# GPS_SCHE.net
KiCad netlist of a schematic drawn in Altium Designer
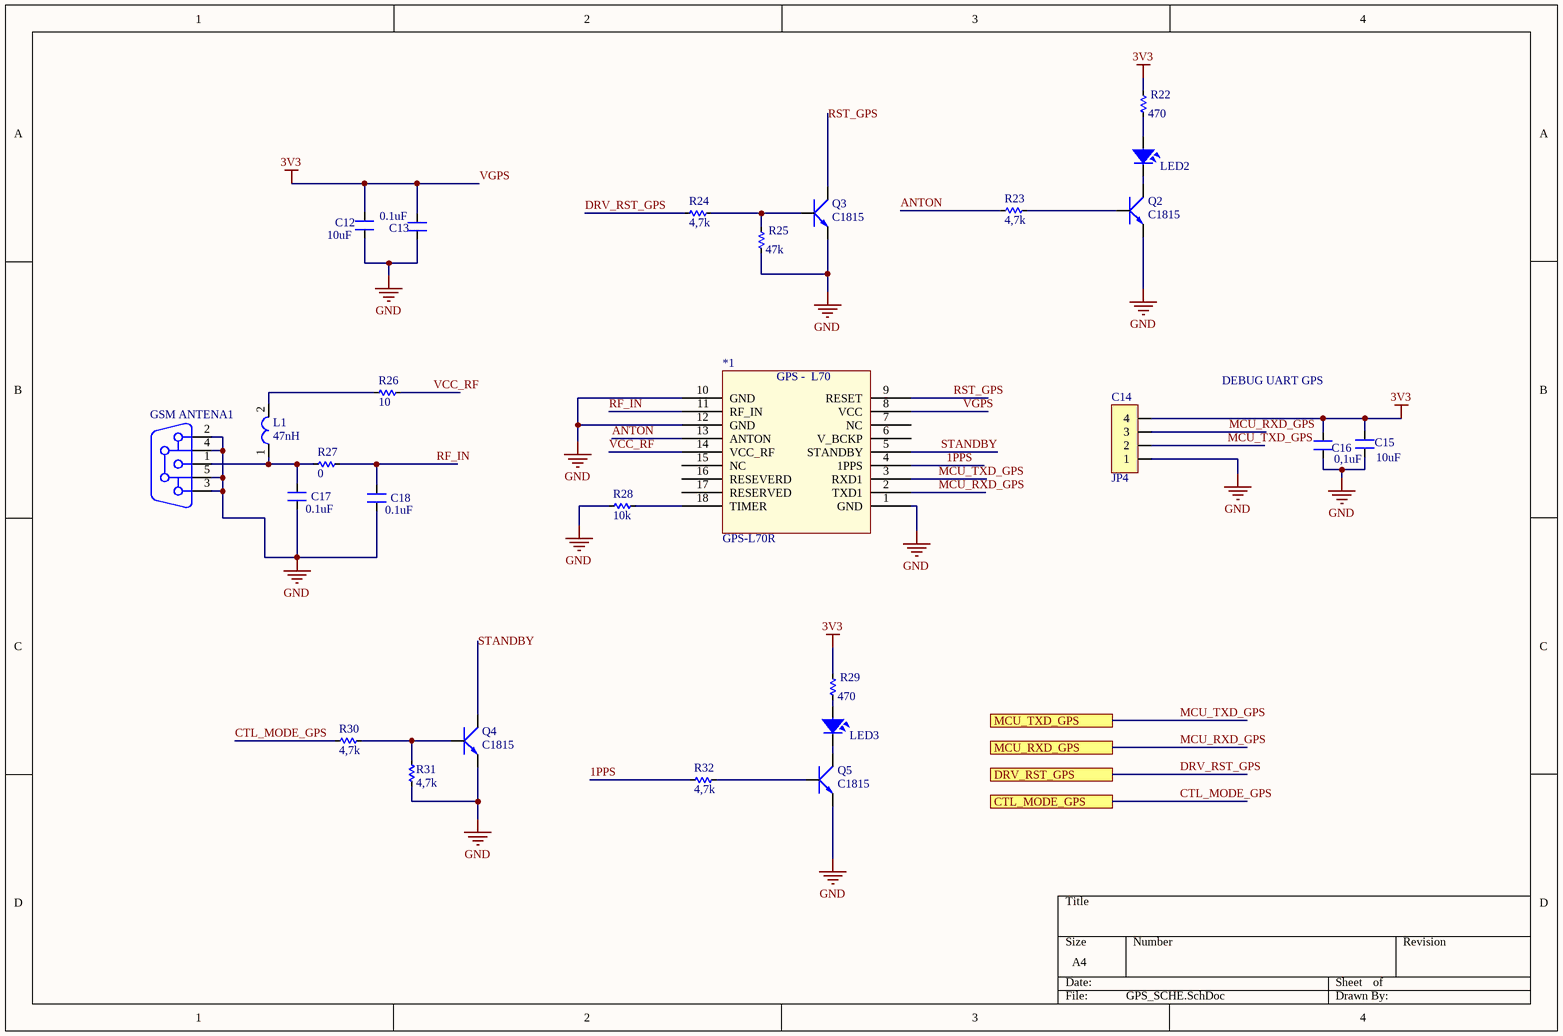
[diagram p0: GPS_SCHE.SchDoc]

(export (version "E")
  (design (tool "Eeschema 10.0.6"))
  (components
    (comp (ref "*1") (value "GPS-L70R") (footprint "GPS_L70R") (libsource (lib "Sim M95") (part "GPS-L70")))
    (comp (ref "C12")
      (value "10uF")
      (footprint "res 0805 - duplicate")
      (fields (field (name "DESIGNED BY") "VanDungEvn"))
      (libsource (lib "syhaunguyen") (part "CN"))
    )
    (comp (ref "C13")
      (value "0.1uF")
      (footprint "res 0805 - duplicate")
      (description "Cap SMD")
      (libsource (lib "PART") (part "CM"))
    )
    (comp (ref "C14")
      (value "JP4")
      (footprint "JP4-C1T")
      (description "WR-PHD 2.54 mm Angled Socket Header")
      (fields
        (field (name "MANUFACTURER") "Würth Elektronik eiSos GmbH")
        (field (name "PARTNO") "613004143121")
        (field (name "CREATED BY") "Karrer Zheng")
      )
      (libsource (lib "LIBRARYabc") (part "JP4"))
    )
    (comp (ref "C15")
      (value "10uF")
      (footprint "res 0805 - duplicate")
      (fields (field (name "DESIGNED BY") "VanDungEvn"))
      (libsource (lib "syhaunguyen") (part "CN"))
    )
    (comp (ref "C16")
      (value "0,1uF")
      (footprint "res 0805 - duplicate")
      (fields (field (name "DESIGNED BY") "VanDungEvn"))
      (libsource (lib "syhaunguyen") (part "CN"))
    )
    (comp (ref "C17")
      (value "0.1uF")
      (footprint "res 0805 - duplicate")
      (description "Cap SMD")
      (libsource (lib "PART") (part "CM"))
    )
    (comp (ref "C18")
      (value "0.1uF")
      (footprint "res 0805 - duplicate")
      (description "Cap SMD")
      (libsource (lib "PART") (part "CM"))
    )
    (comp (ref "GSM ANTENA1")
      (value "~")
      (footprint "anten")
      (description "CONNECTOR ANTEN")
      (fields
        (field (name "PARTNO") "210111003")
        (field (name "MANUFACTURER") "Würth Elektronik eiSos GmbH")
        (field (name "CREATED BY") "Christin Zierenner")
      )
      (libsource (lib "LIBRARYabc") (part "CON Ant"))
    )
    (comp (ref "L1")
      (value "47nH")
      (footprint "res 0805 - duplicate")
      (fields
        (field (name "PARTNO") "78477010")
        (field (name "MANUFACTURER") "Wurth Elektronik")
        (field (name "CREATED BY") "Baojun Chen")
      )
      (libsource (lib "LIBRARYabc") (part "L-SMD-1"))
    )
    (comp (ref "LED2")
      (value "LED")
      (footprint "res 0805 - duplicate")
      (libsource (lib "LIBRARYabc") (part "LED SMD"))
    )
    (comp (ref "LED3")
      (value "LED")
      (footprint "res 0805 - duplicate")
      (libsource (lib "LIBRARYabc") (part "LED SMD"))
    )
    (comp (ref "Q2")
      (value "C1815")
      (footprint "SOT23B")
      (description "NPN 600mW, ECB")
      (libsource (lib "syhaunguyen") (part "C1815"))
    )
    (comp (ref "Q3")
      (value "C1815")
      (footprint "SOT23B")
      (description "NPN 600mW, ECB")
      (libsource (lib "syhaunguyen") (part "C1815"))
    )
    (comp (ref "Q4")
      (value "C1815")
      (footprint "SOT23B")
      (description "NPN 600mW, ECB")
      (libsource (lib "syhaunguyen") (part "C1815"))
    )
    (comp (ref "Q5")
      (value "C1815")
      (footprint "SOT23B")
      (description "NPN 600mW, ECB")
      (libsource (lib "syhaunguyen") (part "C1815"))
    )
    (comp (ref "R22")
      (value "470")
      (footprint "res 0805 - duplicate")
      (description "Resistor")
      (fields
        (field (name "MANUFACTURER") "Generic Components")
        (field (name "PUBLISHER") "Altium Hobart Technology Centre")
      )
      (libsource (lib "LIBRARYabc") (part "Res-SMD"))
    )
    (comp (ref "R23")
      (value "4,7k")
      (footprint "res 0805 - duplicate")
      (description "Resistor")
      (fields
        (field (name "MANUFACTURER") "Generic Components")
        (field (name "PUBLISHER") "Altium Hobart Technology Centre")
      )
      (libsource (lib "LIBRARYabc") (part "Res-SMD"))
    )
    (comp (ref "R24")
      (value "4,7k")
      (footprint "res 0805 - duplicate")
      (description "Resistor")
      (fields
        (field (name "MANUFACTURER") "Generic Components")
        (field (name "PUBLISHER") "Altium Hobart Technology Centre")
      )
      (libsource (lib "LIBRARYabc") (part "Res-SMD"))
    )
    (comp (ref "R25")
      (value "47k")
      (footprint "res 0805 - duplicate")
      (description "Resistor")
      (fields
        (field (name "MANUFACTURER") "Generic Components")
        (field (name "PUBLISHER") "Altium Hobart Technology Centre")
      )
      (libsource (lib "LIBRARYabc") (part "Res-SMD"))
    )
    (comp (ref "R26")
      (value "10")
      (footprint "res 0805 - duplicate")
      (description "Resistor")
      (fields
        (field (name "MANUFACTURER") "Generic Components")
        (field (name "PUBLISHER") "Altium Hobart Technology Centre")
      )
      (libsource (lib "LIBRARYabc") (part "Res-SMD"))
    )
    (comp (ref "R27")
      (value "0")
      (footprint "res 0805 - duplicate")
      (description "Resistor")
      (fields
        (field (name "MANUFACTURER") "Generic Components")
        (field (name "PUBLISHER") "Altium Hobart Technology Centre")
      )
      (libsource (lib "LIBRARYabc") (part "Res-SMD"))
    )
    (comp (ref "R28")
      (value "10k")
      (footprint "res 0805 - duplicate")
      (description "Resistor")
      (fields
        (field (name "MANUFACTURER") "Generic Components")
        (field (name "PUBLISHER") "Altium Hobart Technology Centre")
      )
      (libsource (lib "LIBRARYabc") (part "Res-SMD"))
    )
    (comp (ref "R29")
      (value "470")
      (footprint "res 0805 - duplicate")
      (description "Resistor")
      (fields
        (field (name "MANUFACTURER") "Generic Components")
        (field (name "PUBLISHER") "Altium Hobart Technology Centre")
      )
      (libsource (lib "LIBRARYabc") (part "Res-SMD"))
    )
    (comp (ref "R30")
      (value "4,7k")
      (footprint "res 0805 - duplicate")
      (description "Resistor")
      (fields
        (field (name "MANUFACTURER") "Generic Components")
        (field (name "PUBLISHER") "Altium Hobart Technology Centre")
      )
      (libsource (lib "LIBRARYabc") (part "Res-SMD"))
    )
    (comp (ref "R31")
      (value "4,7k")
      (footprint "res 0805 - duplicate")
      (description "Resistor")
      (fields
        (field (name "MANUFACTURER") "Generic Components")
        (field (name "PUBLISHER") "Altium Hobart Technology Centre")
      )
      (libsource (lib "LIBRARYabc") (part "Res-SMD"))
    )
    (comp (ref "R32")
      (value "4,7k")
      (footprint "res 0805 - duplicate")
      (description "Resistor")
      (fields
        (field (name "MANUFACTURER") "Generic Components")
        (field (name "PUBLISHER") "Altium Hobart Technology Centre")
      )
      (libsource (lib "LIBRARYabc") (part "Res-SMD"))
    )
  )
  (nets
    (net (code "1") (name "/1PPS") (class "Default")
      (node (ref "*1") (pin "4") (pinfunction "1PPS_4") (pintype "passive"))
      (node (ref "R32") (pin "1") (pinfunction "1_1") (pintype "passive"))
    )
    (net (code "2") (name "/ANTON") (class "Default")
      (node (ref "*1") (pin "13") (pinfunction "ANTON_13") (pintype "passive"))
      (node (ref "R23") (pin "1") (pinfunction "1_1") (pintype "passive"))
    )
    (net (code "3") (name "/CTL_MODE_GPS") (class "Default")
      (node (ref "R30") (pin "1") (pinfunction "1_1") (pintype "passive"))
    )
    (net (code "4") (name "/DRV_RST_GPS") (class "Default")
      (node (ref "R24") (pin "1") (pinfunction "1_1") (pintype "passive"))
    )
    (net (code "5") (name "/MCU_RXD_GPS") (class "Default")
      (node (ref "*1") (pin "2") (pinfunction "TXD1_2") (pintype "passive"))
      (node (ref "C14") (pin "3") (pinfunction "3_3") (pintype "passive"))
    )
    (net (code "6") (name "/MCU_TXD_GPS") (class "Default")
      (node (ref "*1") (pin "3") (pinfunction "RXD1_3") (pintype "passive"))
      (node (ref "C14") (pin "2") (pinfunction "2_2") (pintype "passive"))
    )
    (net (code "7") (name "/RF_IN") (class "Default")
      (node (ref "*1") (pin "11") (pinfunction "RF_IN_11") (pintype "passive"))
      (node (ref "C18") (pin "2") (pinfunction "2_2") (pintype "passive"))
      (node (ref "R27") (pin "2") (pinfunction "2_2") (pintype "passive"))
    )
    (net (code "8") (name "/RST_GPS") (class "Default")
      (node (ref "*1") (pin "9") (pinfunction "RESET_9") (pintype "passive"))
      (node (ref "Q3") (pin "2") (pinfunction "C_2") (pintype "passive"))
    )
    (net (code "9") (name "/STANDBY") (class "Default")
      (node (ref "*1") (pin "5") (pinfunction "STANDBY_5") (pintype "passive"))
      (node (ref "Q4") (pin "2") (pinfunction "C_2") (pintype "passive"))
    )
    (net (code "10") (name "/VCC_RF") (class "Default")
      (node (ref "*1") (pin "14") (pinfunction "VCC_RF_14") (pintype "passive"))
      (node (ref "R26") (pin "2") (pinfunction "2_2") (pintype "passive"))
    )
    (net (code "11") (name "3V3") (class "Default")
      (node (ref "*1") (pin "8") (pinfunction "VCC_8") (pintype "passive"))
      (node (ref "C12") (pin "2") (pinfunction "2_2") (pintype "passive"))
      (node (ref "C13") (pin "2") (pinfunction "2_2") (pintype "passive"))
      (node (ref "C14") (pin "4") (pinfunction "4_4") (pintype "passive"))
      (node (ref "C15") (pin "2") (pinfunction "2_2") (pintype "passive"))
      (node (ref "C16") (pin "2") (pinfunction "2_2") (pintype "passive"))
      (node (ref "R22") (pin "2") (pinfunction "2_2") (pintype "passive"))
      (node (ref "R29") (pin "2") (pinfunction "2_2") (pintype "passive"))
    )
    (net (code "12") (name "GND") (class "Default")
      (node (ref "*1") (pin "1") (pinfunction "GND_1") (pintype "passive"))
      (node (ref "*1") (pin "10") (pinfunction "GND_10") (pintype "passive"))
      (node (ref "*1") (pin "12") (pinfunction "GND_12") (pintype "passive"))
      (node (ref "C12") (pin "1") (pinfunction "1_1") (pintype "passive"))
      (node (ref "C13") (pin "1") (pinfunction "1_1") (pintype "passive"))
      (node (ref "C14") (pin "1") (pinfunction "1_1") (pintype "passive"))
      (node (ref "C15") (pin "1") (pinfunction "1_1") (pintype "passive"))
      (node (ref "C16") (pin "1") (pinfunction "1_1") (pintype "passive"))
      (node (ref "C17") (pin "1") (pinfunction "1_1") (pintype "passive"))
      (node (ref "C18") (pin "1") (pinfunction "1_1") (pintype "passive"))
      (node (ref "GSM ANTENA1") (pin "2") (pinfunction "2_2") (pintype "passive"))
      (node (ref "GSM ANTENA1") (pin "3") (pinfunction "3_3") (pintype "passive"))
      (node (ref "GSM ANTENA1") (pin "4") (pinfunction "4_4") (pintype "passive"))
      (node (ref "GSM ANTENA1") (pin "5") (pinfunction "5_5") (pintype "passive"))
      (node (ref "Q2") (pin "1") (pinfunction "E_1") (pintype "passive"))
      (node (ref "Q3") (pin "1") (pinfunction "E_1") (pintype "passive"))
      (node (ref "Q4") (pin "1") (pinfunction "E_1") (pintype "passive"))
      (node (ref "Q5") (pin "1") (pinfunction "E_1") (pintype "passive"))
      (node (ref "R25") (pin "1") (pinfunction "1_1") (pintype "passive"))
      (node (ref "R28") (pin "1") (pinfunction "1_1") (pintype "passive"))
      (node (ref "R31") (pin "1") (pinfunction "1_1") (pintype "passive"))
    )
    (net (code "13") (name "Net-(*1-TIMER)") (class "Default")
      (node (ref "*1") (pin "18") (pinfunction "TIMER_18") (pintype "passive"))
      (node (ref "R28") (pin "2") (pinfunction "2_2") (pintype "passive"))
    )
    (net (code "14") (name "Net-(C17-Pad2)") (class "Default")
      (node (ref "C17") (pin "2") (pinfunction "2_2") (pintype "passive"))
      (node (ref "GSM ANTENA1") (pin "1") (pinfunction "1_1") (pintype "passive"))
      (node (ref "L1") (pin "1") (pinfunction "1_1") (pintype "passive"))
      (node (ref "R27") (pin "1") (pinfunction "1_1") (pintype "passive"))
    )
    (net (code "15") (name "Net-(L1-Pad2)") (class "Default")
      (node (ref "L1") (pin "2") (pinfunction "2_2") (pintype "passive"))
      (node (ref "R26") (pin "1") (pinfunction "1_1") (pintype "passive"))
    )
    (net (code "16") (name "Net-(LED2-Pad1)") (class "Default")
      (node (ref "LED2") (pin "1") (pinfunction "1_1") (pintype "passive"))
      (node (ref "R22") (pin "1") (pinfunction "1_1") (pintype "passive"))
    )
    (net (code "17") (name "Net-(LED3-Pad1)") (class "Default")
      (node (ref "LED3") (pin "1") (pinfunction "1_1") (pintype "passive"))
      (node (ref "R29") (pin "1") (pinfunction "1_1") (pintype "passive"))
    )
    (net (code "18") (name "Net-(Q2-B)") (class "Default")
      (node (ref "Q2") (pin "3") (pinfunction "B_3") (pintype "passive"))
      (node (ref "R23") (pin "2") (pinfunction "2_2") (pintype "passive"))
    )
    (net (code "19") (name "Net-(Q2-C)") (class "Default")
      (node (ref "LED2") (pin "2") (pinfunction "2_2") (pintype "passive"))
      (node (ref "Q2") (pin "2") (pinfunction "C_2") (pintype "passive"))
    )
    (net (code "20") (name "Net-(Q3-B)") (class "Default")
      (node (ref "Q3") (pin "3") (pinfunction "B_3") (pintype "passive"))
      (node (ref "R24") (pin "2") (pinfunction "2_2") (pintype "passive"))
      (node (ref "R25") (pin "2") (pinfunction "2_2") (pintype "passive"))
    )
    (net (code "21") (name "Net-(Q4-B)") (class "Default")
      (node (ref "Q4") (pin "3") (pinfunction "B_3") (pintype "passive"))
      (node (ref "R30") (pin "2") (pinfunction "2_2") (pintype "passive"))
      (node (ref "R31") (pin "2") (pinfunction "2_2") (pintype "passive"))
    )
    (net (code "22") (name "Net-(Q5-B)") (class "Default")
      (node (ref "Q5") (pin "3") (pinfunction "B_3") (pintype "passive"))
      (node (ref "R32") (pin "2") (pinfunction "2_2") (pintype "passive"))
    )
    (net (code "23") (name "Net-(Q5-C)") (class "Default")
      (node (ref "LED3") (pin "2") (pinfunction "2_2") (pintype "passive"))
      (node (ref "Q5") (pin "2") (pinfunction "C_2") (pintype "passive"))
    )
    (net (code "24") (name "unconnected-(*1-NC-Pad7)") (class "Default")
      (node (ref "*1") (pin "7") (pinfunction "NC_7") (pintype "passive"))
    )
    (net (code "25") (name "unconnected-(*1-NC-Pad15)") (class "Default")
      (node (ref "*1") (pin "15") (pinfunction "NC_15") (pintype "passive"))
    )
    (net (code "26") (name "unconnected-(*1-RESERVED-Pad17)") (class "Default")
      (node (ref "*1") (pin "17") (pinfunction "RESERVED_17") (pintype "passive"))
    )
    (net (code "27") (name "unconnected-(*1-RESEVERD-Pad16)") (class "Default")
      (node (ref "*1") (pin "16") (pinfunction "RESEVERD_16") (pintype "passive"))
    )
    (net (code "28") (name "unconnected-(*1-V_BCKP-Pad6)") (class "Default")
      (node (ref "*1") (pin "6") (pinfunction "V_BCKP_6") (pintype "passive"))
    )
  )
)
